# 18650_1S3P_Smart.net
KiCad netlist of a schematic drawn in EAGLE
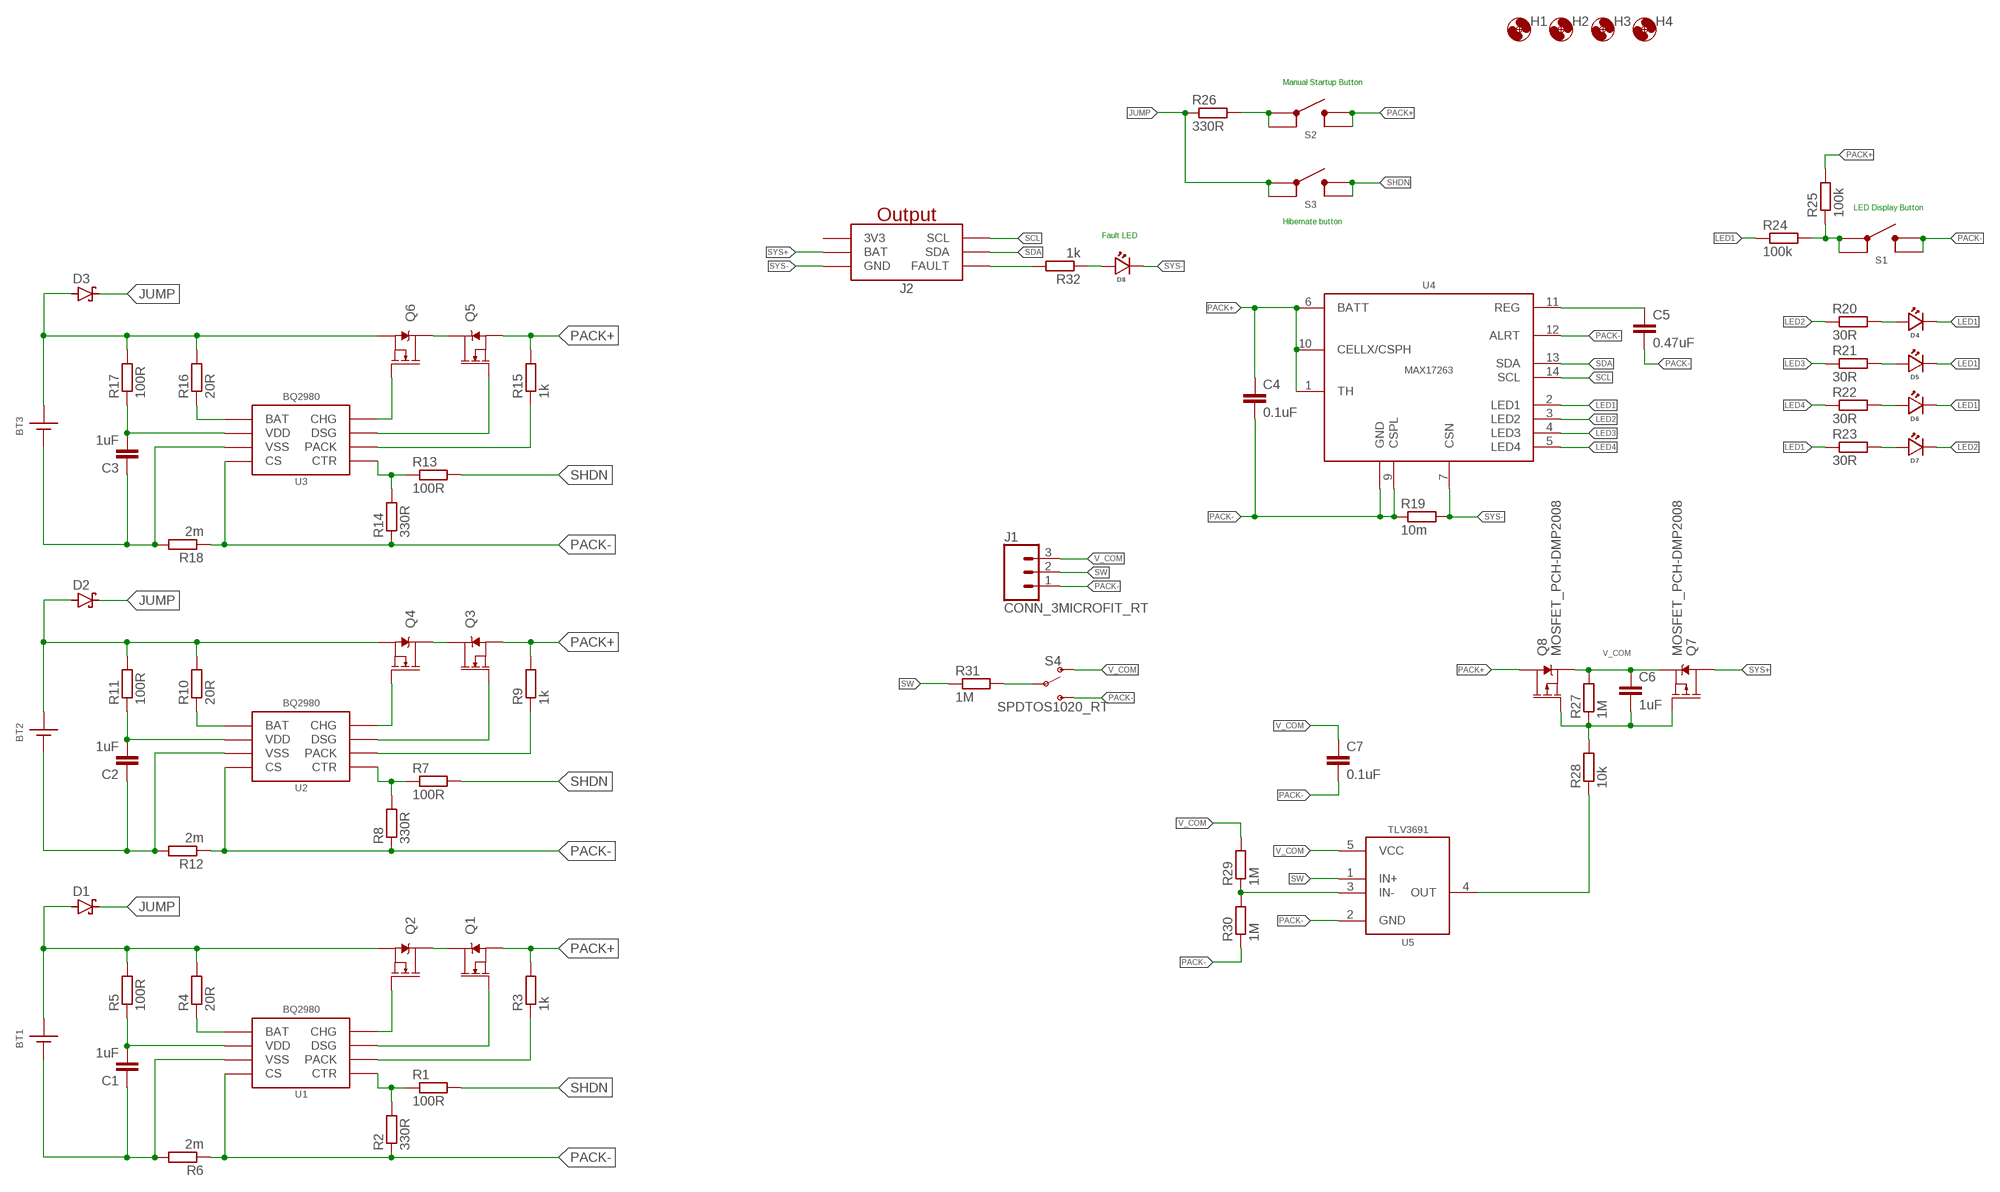
[diagram p0: schematic, sheet 1]

(export (version "E")
  (design (tool "Eeschema 10.0.6"))
  (components
    (comp (ref "BT1")
      (value "186501042P_NOSILK")
      (footprint "eagle-import:BATT_1042P_NOSILK")
      (fields (field (name "MF") "Keystone") (field (name "MPN") "1042P"))
      (libsource (lib "eagle-import") (part "186501042P_NOSILK"))
    )
    (comp (ref "BT2")
      (value "186501042P_NOSILK")
      (footprint "eagle-import:BATT_1042P_NOSILK")
      (fields (field (name "MF") "Keystone") (field (name "MPN") "1042P"))
      (libsource (lib "eagle-import") (part "186501042P_NOSILK"))
    )
    (comp (ref "BT3")
      (value "186501042P_NOSILK")
      (footprint "eagle-import:BATT_1042P_NOSILK")
      (fields (field (name "MF") "Keystone") (field (name "MPN") "1042P"))
      (libsource (lib "eagle-import") (part "186501042P_NOSILK"))
    )
    (comp (ref "C1")
      (value "1uF")
      (footprint "eagle-import:C0603")
      (fields (field (name "MF") "Yaiyo Yuden") (field (name "MPN") "EMK107BJ105KA-T"))
      (libsource (lib "eagle-import") (part "C-EUC06031UF"))
    )
    (comp (ref "C2")
      (value "1uF")
      (footprint "eagle-import:C0603")
      (fields (field (name "MF") "Yaiyo Yuden") (field (name "MPN") "EMK107BJ105KA-T"))
      (libsource (lib "eagle-import") (part "C-EUC06031UF"))
    )
    (comp (ref "C3")
      (value "1uF")
      (footprint "eagle-import:C0603")
      (fields (field (name "MF") "Yaiyo Yuden") (field (name "MPN") "EMK107BJ105KA-T"))
      (libsource (lib "eagle-import") (part "C-EUC06031UF"))
    )
    (comp (ref "C4")
      (value "0.1uF")
      (footprint "eagle-import:C0603")
      (fields (field (name "MF") "Murata") (field (name "MPN") "GCM188R71E104KA57D"))
      (libsource (lib "eagle-import") (part "C-EUC06030.1UF"))
    )
    (comp (ref "C5")
      (value "0.47uF")
      (footprint "eagle-import:C0603")
      (fields (field (name "MF") "Samsung") (field (name "MPN") "CL10B474KA8NNNC"))
      (libsource (lib "eagle-import") (part "C-EUC06030.47UF"))
    )
    (comp (ref "C6")
      (value "1uF")
      (footprint "eagle-import:C0603")
      (fields (field (name "MF") "Yaiyo Yuden") (field (name "MPN") "EMK107BJ105KA-T"))
      (libsource (lib "eagle-import") (part "C-EUC06031UF"))
    )
    (comp (ref "C7")
      (value "0.1uF")
      (footprint "eagle-import:C0603")
      (fields (field (name "MF") "Murata") (field (name "MPN") "GCM188R71E104KA57D"))
      (libsource (lib "eagle-import") (part "C-EUC06030.1UF"))
    )
    (comp (ref "D1")
      (value "DIODE_SCHOTTKYSOD-323")
      (footprint "eagle-import:SOD323-R")
      (fields
        (field (name "DIGIKEY") "BAT54WS-FDICT-ND")
        (field (name "MF") "Diodes Inc")
        (field (name "MPN") "BAT54WS-7-F")
      )
      (libsource (lib "eagle-import") (part "DIODE_SCHOTTKYSOD-323"))
    )
    (comp (ref "D2")
      (value "DIODE_SCHOTTKYSOD-323")
      (footprint "eagle-import:SOD323-R")
      (fields
        (field (name "DIGIKEY") "BAT54WS-FDICT-ND")
        (field (name "MF") "Diodes Inc")
        (field (name "MPN") "BAT54WS-7-F")
      )
      (libsource (lib "eagle-import") (part "DIODE_SCHOTTKYSOD-323"))
    )
    (comp (ref "D3")
      (value "DIODE_SCHOTTKYSOD-323")
      (footprint "eagle-import:SOD323-R")
      (fields
        (field (name "DIGIKEY") "BAT54WS-FDICT-ND")
        (field (name "MF") "Diodes Inc")
        (field (name "MPN") "BAT54WS-7-F")
      )
      (libsource (lib "eagle-import") (part "DIODE_SCHOTTKYSOD-323"))
    )
    (comp (ref "D4")
      (value "LED1206_BOTTOM")
      (footprint "eagle-import:LED_1206_BOTTOM")
      (libsource (lib "eagle-import") (part "LED1206_BOTTOM"))
    )
    (comp (ref "D5")
      (value "LED1206_BOTTOM")
      (footprint "eagle-import:LED_1206_BOTTOM")
      (libsource (lib "eagle-import") (part "LED1206_BOTTOM"))
    )
    (comp (ref "D6")
      (value "LED1206_BOTTOM")
      (footprint "eagle-import:LED_1206_BOTTOM")
      (libsource (lib "eagle-import") (part "LED1206_BOTTOM"))
    )
    (comp (ref "D7")
      (value "LED1206_BOTTOM")
      (footprint "eagle-import:LED_1206_BOTTOM")
      (libsource (lib "eagle-import") (part "LED1206_BOTTOM"))
    )
    (comp (ref "D8")
      (value "LED1206_BOTTOM")
      (footprint "eagle-import:LED_1206_BOTTOM")
      (libsource (lib "eagle-import") (part "LED1206_BOTTOM"))
    )
    (comp (ref "H1")
      (value "MOUNTING_HOLE2_NP")
      (footprint "eagle-import:2_56")
      (fields (field (name "MPN") "DNP"))
      (libsource (lib "eagle-import") (part "MOUNTING_HOLE2_NP"))
    )
    (comp (ref "H2")
      (value "MOUNTING_HOLE2_NP")
      (footprint "eagle-import:2_56")
      (fields (field (name "MPN") "DNP"))
      (libsource (lib "eagle-import") (part "MOUNTING_HOLE2_NP"))
    )
    (comp (ref "H3")
      (value "MOUNTING_HOLE2_NP")
      (footprint "eagle-import:2_56")
      (fields (field (name "MPN") "DNP"))
      (libsource (lib "eagle-import") (part "MOUNTING_HOLE2_NP"))
    )
    (comp (ref "H4")
      (value "MOUNTING_HOLE2_NP")
      (footprint "eagle-import:2_56")
      (fields (field (name "MPN") "DNP"))
      (libsource (lib "eagle-import") (part "MOUNTING_HOLE2_NP"))
    )
    (comp (ref "J1")
      (value "CONN_3MICROFIT_RT")
      (footprint "eagle-import:1X3_MICROFIT_RT")
      (fields (field (name "MF") "Molex") (field (name "MPN") "0436500300"))
      (libsource (lib "eagle-import") (part "CONN_3MICROFIT_RT"))
    )
    (comp (ref "J2")
      (value "GEMS_POWER_PLUGOUTPUT")
      (footprint "eagle-import:2X3_MICROFIT_RT")
      (fields (field (name "DISP") "Output") (field (name "MF") "Molex") (field (name "MPN") "0430450600"))
      (libsource (lib "eagle-import") (part "GEMS_POWER_PLUGOUTPUT"))
    )
    (comp (ref "Q1")
      (value "MOSFET-NCH-AON7522E")
      (footprint "eagle-import:DFN3X3A_8L_EP1_P")
      (fields (field (name "MF") "Alpha & Omega") (field (name "MPN") "AON7522E"))
      (libsource (lib "eagle-import") (part "MOSFET-NCH-AON7522E"))
    )
    (comp (ref "Q2")
      (value "MOSFET-NCH-AON7522E")
      (footprint "eagle-import:DFN3X3A_8L_EP1_P")
      (fields (field (name "MF") "Alpha & Omega") (field (name "MPN") "AON7522E"))
      (libsource (lib "eagle-import") (part "MOSFET-NCH-AON7522E"))
    )
    (comp (ref "Q3")
      (value "MOSFET-NCH-AON7522E")
      (footprint "eagle-import:DFN3X3A_8L_EP1_P")
      (fields (field (name "MF") "Alpha & Omega") (field (name "MPN") "AON7522E"))
      (libsource (lib "eagle-import") (part "MOSFET-NCH-AON7522E"))
    )
    (comp (ref "Q4")
      (value "MOSFET-NCH-AON7522E")
      (footprint "eagle-import:DFN3X3A_8L_EP1_P")
      (fields (field (name "MF") "Alpha & Omega") (field (name "MPN") "AON7522E"))
      (libsource (lib "eagle-import") (part "MOSFET-NCH-AON7522E"))
    )
    (comp (ref "Q5")
      (value "MOSFET-NCH-AON7522E")
      (footprint "eagle-import:DFN3X3A_8L_EP1_P")
      (fields (field (name "MF") "Alpha & Omega") (field (name "MPN") "AON7522E"))
      (libsource (lib "eagle-import") (part "MOSFET-NCH-AON7522E"))
    )
    (comp (ref "Q6")
      (value "MOSFET-NCH-AON7522E")
      (footprint "eagle-import:DFN3X3A_8L_EP1_P")
      (fields (field (name "MF") "Alpha & Omega") (field (name "MPN") "AON7522E"))
      (libsource (lib "eagle-import") (part "MOSFET-NCH-AON7522E"))
    )
    (comp (ref "Q7")
      (value "MOSFET_PCH-DMP2008")
      (footprint "eagle-import:POWERDI3333-8")
      (libsource (lib "eagle-import") (part "MOSFET_PCH-DMP2008"))
    )
    (comp (ref "Q8")
      (value "MOSFET_PCH-DMP2008")
      (footprint "eagle-import:POWERDI3333-8")
      (libsource (lib "eagle-import") (part "MOSFET_PCH-DMP2008"))
    )
    (comp (ref "R1")
      (value "100R")
      (footprint "eagle-import:R0603")
      (fields
        (field (name "MF") "Yageo")
        (field (name "MPN") "RC0603FR-07100RL")
        (field (name "VALUE_PART") "100")
      )
      (libsource (lib "eagle-import") (part "R-EU_R0603100"))
    )
    (comp (ref "R2")
      (value "330R")
      (footprint "eagle-import:R0603")
      (fields
        (field (name "MF") "Yageo")
        (field (name "MPN") "RC0603FR-07330RL")
        (field (name "VALUE_PART") "330")
      )
      (libsource (lib "eagle-import") (part "R-EU_R0603330"))
    )
    (comp (ref "R3")
      (value "1k")
      (footprint "eagle-import:R0603")
      (fields (field (name "MF") "Yageo") (field (name "MPN") "AC0603FR-071KL"))
      (libsource (lib "eagle-import") (part "R-EU_R06031K"))
    )
    (comp (ref "R4")
      (value "20R")
      (footprint "eagle-import:R0603")
      (fields
        (field (name "MF") "Yageo")
        (field (name "MPN") "RC0603FR-0720RL")
        (field (name "VALUE_PART") "20")
      )
      (libsource (lib "eagle-import") (part "R-EU_R060320"))
    )
    (comp (ref "R5")
      (value "100R")
      (footprint "eagle-import:R0603")
      (fields
        (field (name "MF") "Yageo")
        (field (name "MPN") "RC0603FR-07100RL")
        (field (name "VALUE_PART") "100")
      )
      (libsource (lib "eagle-import") (part "R-EU_R0603100"))
    )
    (comp (ref "R6")
      (value "2m")
      (footprint "eagle-import:R0805")
      (fields (field (name "MF") "Rohm") (field (name "MPN") "PMR10EZPFV2L00"))
      (libsource (lib "eagle-import") (part "R-EU_R08050.002"))
    )
    (comp (ref "R7")
      (value "100R")
      (footprint "eagle-import:R0603")
      (fields
        (field (name "MF") "Yageo")
        (field (name "MPN") "RC0603FR-07100RL")
        (field (name "VALUE_PART") "100")
      )
      (libsource (lib "eagle-import") (part "R-EU_R0603100"))
    )
    (comp (ref "R8")
      (value "330R")
      (footprint "eagle-import:R0603")
      (fields
        (field (name "MF") "Yageo")
        (field (name "MPN") "RC0603FR-07330RL")
        (field (name "VALUE_PART") "330")
      )
      (libsource (lib "eagle-import") (part "R-EU_R0603330"))
    )
    (comp (ref "R9")
      (value "1k")
      (footprint "eagle-import:R0603")
      (fields (field (name "MF") "Yageo") (field (name "MPN") "AC0603FR-071KL"))
      (libsource (lib "eagle-import") (part "R-EU_R06031K"))
    )
    (comp (ref "R10")
      (value "20R")
      (footprint "eagle-import:R0603")
      (fields
        (field (name "MF") "Yageo")
        (field (name "MPN") "RC0603FR-0720RL")
        (field (name "VALUE_PART") "20")
      )
      (libsource (lib "eagle-import") (part "R-EU_R060320"))
    )
    (comp (ref "R11")
      (value "100R")
      (footprint "eagle-import:R0603")
      (fields
        (field (name "MF") "Yageo")
        (field (name "MPN") "RC0603FR-07100RL")
        (field (name "VALUE_PART") "100")
      )
      (libsource (lib "eagle-import") (part "R-EU_R0603100"))
    )
    (comp (ref "R12")
      (value "2m")
      (footprint "eagle-import:R0805")
      (fields (field (name "MF") "Rohm") (field (name "MPN") "PMR10EZPFV2L00"))
      (libsource (lib "eagle-import") (part "R-EU_R08050.002"))
    )
    (comp (ref "R13")
      (value "100R")
      (footprint "eagle-import:R0603")
      (fields
        (field (name "MF") "Yageo")
        (field (name "MPN") "RC0603FR-07100RL")
        (field (name "VALUE_PART") "100")
      )
      (libsource (lib "eagle-import") (part "R-EU_R0603100"))
    )
    (comp (ref "R14")
      (value "330R")
      (footprint "eagle-import:R0603")
      (fields
        (field (name "MF") "Yageo")
        (field (name "MPN") "RC0603FR-07330RL")
        (field (name "VALUE_PART") "330")
      )
      (libsource (lib "eagle-import") (part "R-EU_R0603330"))
    )
    (comp (ref "R15")
      (value "1k")
      (footprint "eagle-import:R0603")
      (fields (field (name "MF") "Yageo") (field (name "MPN") "AC0603FR-071KL"))
      (libsource (lib "eagle-import") (part "R-EU_R06031K"))
    )
    (comp (ref "R16")
      (value "20R")
      (footprint "eagle-import:R0603")
      (fields
        (field (name "MF") "Yageo")
        (field (name "MPN") "RC0603FR-0720RL")
        (field (name "VALUE_PART") "20")
      )
      (libsource (lib "eagle-import") (part "R-EU_R060320"))
    )
    (comp (ref "R17")
      (value "100R")
      (footprint "eagle-import:R0603")
      (fields
        (field (name "MF") "Yageo")
        (field (name "MPN") "RC0603FR-07100RL")
        (field (name "VALUE_PART") "100")
      )
      (libsource (lib "eagle-import") (part "R-EU_R0603100"))
    )
    (comp (ref "R18")
      (value "2m")
      (footprint "eagle-import:R0805")
      (fields (field (name "MF") "Rohm") (field (name "MPN") "PMR10EZPFV2L00"))
      (libsource (lib "eagle-import") (part "R-EU_R08050.002"))
    )
    (comp (ref "R19")
      (value "10m")
      (footprint "eagle-import:R0805")
      (fields (field (name "MF") "Bourns") (field (name "MPN") "CRF0805-FZ-R010ELF"))
      (libsource (lib "eagle-import") (part "R-EU_R08050.01"))
    )
    (comp (ref "R20")
      (value "30R")
      (footprint "eagle-import:R0603")
      (fields
        (field (name "MF") "Yageo")
        (field (name "MPN") "RC0603FR-0730RL")
        (field (name "VALUE_PART") "30")
      )
      (libsource (lib "eagle-import") (part "R-EU_R060330"))
    )
    (comp (ref "R21")
      (value "30R")
      (footprint "eagle-import:R0603")
      (fields
        (field (name "MF") "Yageo")
        (field (name "MPN") "RC0603FR-0730RL")
        (field (name "VALUE_PART") "30")
      )
      (libsource (lib "eagle-import") (part "R-EU_R060330"))
    )
    (comp (ref "R22")
      (value "30R")
      (footprint "eagle-import:R0603")
      (fields
        (field (name "MF") "Yageo")
        (field (name "MPN") "RC0603FR-0730RL")
        (field (name "VALUE_PART") "30")
      )
      (libsource (lib "eagle-import") (part "R-EU_R060330"))
    )
    (comp (ref "R23")
      (value "30R")
      (footprint "eagle-import:R0603")
      (fields
        (field (name "MF") "Yageo")
        (field (name "MPN") "RC0603FR-0730RL")
        (field (name "VALUE_PART") "30")
      )
      (libsource (lib "eagle-import") (part "R-EU_R060330"))
    )
    (comp (ref "R24")
      (value "100k")
      (footprint "eagle-import:R0603")
      (fields (field (name "MF") "Yageo") (field (name "MPN") "RC0603FR-07100KL"))
      (libsource (lib "eagle-import") (part "R-EU_R0603100K"))
    )
    (comp (ref "R25")
      (value "100k")
      (footprint "eagle-import:R0603")
      (fields (field (name "MF") "Yageo") (field (name "MPN") "RC0603FR-07100KL"))
      (libsource (lib "eagle-import") (part "R-EU_R0603100K"))
    )
    (comp (ref "R26")
      (value "330R")
      (footprint "eagle-import:R0603")
      (fields
        (field (name "MF") "Yageo")
        (field (name "MPN") "RC0603FR-07330RL")
        (field (name "VALUE_PART") "330")
      )
      (libsource (lib "eagle-import") (part "R-EU_R0603330"))
    )
    (comp (ref "R27")
      (value "1M")
      (footprint "eagle-import:R0603")
      (fields (field (name "MF") "Panasonic") (field (name "MPN") "ERJ-3EKF1004V"))
      (libsource (lib "eagle-import") (part "R-EU_R06031M"))
    )
    (comp (ref "R28")
      (value "10k")
      (footprint "eagle-import:R0603")
      (fields (field (name "MF") "Yageo") (field (name "MPN") "RC0603FR-0710KL"))
      (libsource (lib "eagle-import") (part "R-EU_R060310K"))
    )
    (comp (ref "R29")
      (value "1M")
      (footprint "eagle-import:R0603")
      (fields (field (name "MF") "Panasonic") (field (name "MPN") "ERJ-3EKF1004V"))
      (libsource (lib "eagle-import") (part "R-EU_R06031M"))
    )
    (comp (ref "R30")
      (value "1M")
      (footprint "eagle-import:R0603")
      (fields (field (name "MF") "Panasonic") (field (name "MPN") "ERJ-3EKF1004V"))
      (libsource (lib "eagle-import") (part "R-EU_R06031M"))
    )
    (comp (ref "R31")
      (value "1M")
      (footprint "eagle-import:R0603")
      (fields (field (name "MF") "Panasonic") (field (name "MPN") "ERJ-3EKF1004V"))
      (libsource (lib "eagle-import") (part "R-EU_R06031M"))
    )
    (comp (ref "R32")
      (value "1k")
      (footprint "eagle-import:R0603")
      (fields (field (name "MF") "Yageo") (field (name "MPN") "AC0603FR-071KL"))
      (libsource (lib "eagle-import") (part "R-EU_R06031K"))
    )
    (comp (ref "S1")
      (value "BUTTON6X6_TH")
      (footprint "eagle-import:SWITCH_6MM_TH")
      (fields (field (name "MF") "TE Connectivity") (field (name "MPN") "1825910-6"))
      (libsource (lib "eagle-import") (part "BUTTON6X6_TH"))
    )
    (comp (ref "S2")
      (value "BUTTON6X6_TH")
      (footprint "eagle-import:SWITCH_6MM_TH")
      (fields (field (name "MF") "TE Connectivity") (field (name "MPN") "1825910-6"))
      (libsource (lib "eagle-import") (part "BUTTON6X6_TH"))
    )
    (comp (ref "S3")
      (value "BUTTON6X6_TH")
      (footprint "eagle-import:SWITCH_6MM_TH")
      (fields (field (name "MF") "TE Connectivity") (field (name "MPN") "1825910-6"))
      (libsource (lib "eagle-import") (part "BUTTON6X6_TH"))
    )
    (comp (ref "S4")
      (value "SPDTOS1020_RT")
      (footprint "eagle-import:OS102011MA1QN1")
      (fields (field (name "MF") "C&K") (field (name "MPN") "OS102011MA1QN1"))
      (libsource (lib "eagle-import") (part "SPDTOS1020_RT"))
    )
    (comp (ref "U1")
      (value "BQ2980RUG")
      (footprint "eagle-import:RUG_S-PQFP-N8")
      (fields (field (name "MF") "TI") (field (name "MPN") "BQ298000RUGT"))
      (libsource (lib "eagle-import") (part "BQ2980RUG"))
    )
    (comp (ref "U2")
      (value "BQ2980RUG")
      (footprint "eagle-import:RUG_S-PQFP-N8")
      (fields (field (name "MF") "TI") (field (name "MPN") "BQ298000RUGT"))
      (libsource (lib "eagle-import") (part "BQ2980RUG"))
    )
    (comp (ref "U3")
      (value "BQ2980RUG")
      (footprint "eagle-import:RUG_S-PQFP-N8")
      (fields (field (name "MF") "TI") (field (name "MPN") "BQ298000RUGT"))
      (libsource (lib "eagle-import") (part "BQ2980RUG"))
    )
    (comp (ref "U4")
      (value "MAX17263")
      (footprint "eagle-import:DFN_14_3X3")
      (fields (field (name "MF") "Maxim") (field (name "MPN") "MAX17263LETD+T"))
      (libsource (lib "eagle-import") (part "MAX17263"))
    )
    (comp (ref "U5")
      (value "TLV3691DCK")
      (footprint "eagle-import:DCK_R-PDSO-G5")
      (fields (field (name "MF") "TI") (field (name "MPN") "TLV3691IDCKR"))
      (libsource (lib "eagle-import") (part "TLV3691DCK"))
    )
  )
  (nets
    (net (code "1") (name "/3V3") (class "Default")
      (node (ref "J2") (pin "5") (pinfunction "3V3_5") (pintype "power_in"))
    )
    (net (code "2") (name "JUMP") (class "Default")
      (node (ref "D1") (pin "C") (pinfunction "C_C") (pintype "passive"))
      (node (ref "D2") (pin "C") (pinfunction "C_C") (pintype "passive"))
      (node (ref "D3") (pin "C") (pinfunction "C_C") (pintype "passive"))
      (node (ref "R26") (pin "1") (pinfunction "1_1") (pintype "passive"))
      (node (ref "S3") (pin "1") (pinfunction "1_1") (pintype "bidirectional"))
      (node (ref "S3") (pin "2") (pinfunction "2_2") (pintype "bidirectional"))
    )
    (net (code "3") (name "LED1") (class "Default")
      (node (ref "D4") (pin "CATHODE") (pinfunction "CATHODE_CATHODE") (pintype "power_in"))
      (node (ref "D5") (pin "CATHODE") (pinfunction "CATHODE_CATHODE") (pintype "power_in"))
      (node (ref "D6") (pin "CATHODE") (pinfunction "CATHODE_CATHODE") (pintype "power_in"))
      (node (ref "R23") (pin "1") (pinfunction "1_1") (pintype "passive"))
      (node (ref "R24") (pin "1") (pinfunction "1_1") (pintype "passive"))
      (node (ref "U4") (pin "2") (pinfunction "LED1_2") (pintype "bidirectional"))
    )
    (net (code "4") (name "LED2") (class "Default")
      (node (ref "D7") (pin "CATHODE") (pinfunction "CATHODE_CATHODE") (pintype "power_in"))
      (node (ref "R20") (pin "1") (pinfunction "1_1") (pintype "passive"))
      (node (ref "U4") (pin "3") (pinfunction "LED2_3") (pintype "bidirectional"))
    )
    (net (code "5") (name "LED3") (class "Default")
      (node (ref "R21") (pin "1") (pinfunction "1_1") (pintype "passive"))
      (node (ref "U4") (pin "4") (pinfunction "LED3_4") (pintype "bidirectional"))
    )
    (net (code "6") (name "LED4") (class "Default")
      (node (ref "R22") (pin "1") (pinfunction "1_1") (pintype "passive"))
      (node (ref "U4") (pin "5") (pinfunction "LED4_5") (pintype "bidirectional"))
    )
    (net (code "7") (name "Net-(BT1-+)") (class "Default")
      (node (ref "BT1") (pin "BATT+") (pinfunction "+_BATT+") (pintype "power_in"))
      (node (ref "D1") (pin "A") (pinfunction "A_A") (pintype "passive"))
      (node (ref "Q2") (pin "S@1") (pinfunction "S_S@1") (pintype "bidirectional"))
      (node (ref "Q2") (pin "S@2") (pinfunction "S_S@2") (pintype "bidirectional"))
      (node (ref "Q2") (pin "S@3") (pinfunction "S_S@3") (pintype "bidirectional"))
      (node (ref "R4") (pin "2") (pinfunction "2_2") (pintype "passive"))
      (node (ref "R5") (pin "2") (pinfunction "2_2") (pintype "passive"))
    )
    (net (code "8") (name "Net-(BT1--)") (class "Default")
      (node (ref "BT1") (pin "BATT-") (pinfunction "-_BATT-") (pintype "power_in"))
      (node (ref "C1") (pin "1") (pinfunction "1_1") (pintype "passive"))
      (node (ref "R6") (pin "2") (pinfunction "2_2") (pintype "passive"))
      (node (ref "U1") (pin "3") (pinfunction "VSS_3") (pintype "power_in"))
    )
    (net (code "9") (name "Net-(BT2-+)") (class "Default")
      (node (ref "BT2") (pin "BATT+") (pinfunction "+_BATT+") (pintype "power_in"))
      (node (ref "D2") (pin "A") (pinfunction "A_A") (pintype "passive"))
      (node (ref "Q4") (pin "S@1") (pinfunction "S_S@1") (pintype "bidirectional"))
      (node (ref "Q4") (pin "S@2") (pinfunction "S_S@2") (pintype "bidirectional"))
      (node (ref "Q4") (pin "S@3") (pinfunction "S_S@3") (pintype "bidirectional"))
      (node (ref "R10") (pin "2") (pinfunction "2_2") (pintype "passive"))
      (node (ref "R11") (pin "2") (pinfunction "2_2") (pintype "passive"))
    )
    (net (code "10") (name "Net-(BT2--)") (class "Default")
      (node (ref "BT2") (pin "BATT-") (pinfunction "-_BATT-") (pintype "power_in"))
      (node (ref "C2") (pin "1") (pinfunction "1_1") (pintype "passive"))
      (node (ref "R12") (pin "2") (pinfunction "2_2") (pintype "passive"))
      (node (ref "U2") (pin "3") (pinfunction "VSS_3") (pintype "power_in"))
    )
    (net (code "11") (name "Net-(BT3-+)") (class "Default")
      (node (ref "BT3") (pin "BATT+") (pinfunction "+_BATT+") (pintype "power_in"))
      (node (ref "D3") (pin "A") (pinfunction "A_A") (pintype "passive"))
      (node (ref "Q6") (pin "S@1") (pinfunction "S_S@1") (pintype "bidirectional"))
      (node (ref "Q6") (pin "S@2") (pinfunction "S_S@2") (pintype "bidirectional"))
      (node (ref "Q6") (pin "S@3") (pinfunction "S_S@3") (pintype "bidirectional"))
      (node (ref "R16") (pin "2") (pinfunction "2_2") (pintype "passive"))
      (node (ref "R17") (pin "2") (pinfunction "2_2") (pintype "passive"))
    )
    (net (code "12") (name "Net-(BT3--)") (class "Default")
      (node (ref "BT3") (pin "BATT-") (pinfunction "-_BATT-") (pintype "power_in"))
      (node (ref "C3") (pin "1") (pinfunction "1_1") (pintype "passive"))
      (node (ref "R18") (pin "2") (pinfunction "2_2") (pintype "passive"))
      (node (ref "U3") (pin "3") (pinfunction "VSS_3") (pintype "power_in"))
    )
    (net (code "13") (name "Net-(D4-PadANODE)") (class "Default")
      (node (ref "D4") (pin "ANODE") (pinfunction "ANODE_ANODE") (pintype "power_in"))
      (node (ref "R20") (pin "2") (pinfunction "2_2") (pintype "passive"))
    )
    (net (code "14") (name "Net-(D5-PadANODE)") (class "Default")
      (node (ref "D5") (pin "ANODE") (pinfunction "ANODE_ANODE") (pintype "power_in"))
      (node (ref "R21") (pin "2") (pinfunction "2_2") (pintype "passive"))
    )
    (net (code "15") (name "Net-(D6-PadANODE)") (class "Default")
      (node (ref "D6") (pin "ANODE") (pinfunction "ANODE_ANODE") (pintype "power_in"))
      (node (ref "R22") (pin "2") (pinfunction "2_2") (pintype "passive"))
    )
    (net (code "16") (name "Net-(D7-PadANODE)") (class "Default")
      (node (ref "D7") (pin "ANODE") (pinfunction "ANODE_ANODE") (pintype "power_in"))
      (node (ref "R23") (pin "2") (pinfunction "2_2") (pintype "passive"))
    )
    (net (code "17") (name "Net-(D8-PadANODE)") (class "Default")
      (node (ref "D8") (pin "ANODE") (pinfunction "ANODE_ANODE") (pintype "power_in"))
      (node (ref "R32") (pin "1") (pinfunction "1_1") (pintype "passive"))
    )
    (net (code "18") (name "Net-(J2-FAULT)") (class "Default")
      (node (ref "J2") (pin "1") (pinfunction "FAULT_1") (pintype "bidirectional"))
      (node (ref "R32") (pin "2") (pinfunction "2_2") (pintype "passive"))
    )
    (net (code "19") (name "Net-(Q1-PadD)") (class "Default")
      (node (ref "Q1") (pin "D") (pinfunction "D_D") (pintype "bidirectional"))
      (node (ref "Q2") (pin "D") (pinfunction "D_D") (pintype "bidirectional"))
    )
    (net (code "20") (name "Net-(Q3-PadD)") (class "Default")
      (node (ref "Q3") (pin "D") (pinfunction "D_D") (pintype "bidirectional"))
      (node (ref "Q4") (pin "D") (pinfunction "D_D") (pintype "bidirectional"))
    )
    (net (code "21") (name "Net-(Q5-PadD)") (class "Default")
      (node (ref "Q5") (pin "D") (pinfunction "D_D") (pintype "bidirectional"))
      (node (ref "Q6") (pin "D") (pinfunction "D_D") (pintype "bidirectional"))
    )
    (net (code "22") (name "Net-(Q7-G)") (class "Default")
      (node (ref "C6") (pin "2") (pinfunction "2_2") (pintype "passive"))
      (node (ref "Q7") (pin "4") (pinfunction "G_4") (pintype "bidirectional"))
      (node (ref "Q8") (pin "4") (pinfunction "G_4") (pintype "bidirectional"))
      (node (ref "R27") (pin "1") (pinfunction "1_1") (pintype "passive"))
      (node (ref "R28") (pin "2") (pinfunction "2_2") (pintype "passive"))
    )
    (net (code "23") (name "Net-(R24-Pad2)") (class "Default")
      (node (ref "R24") (pin "2") (pinfunction "2_2") (pintype "passive"))
      (node (ref "R25") (pin "1") (pinfunction "1_1") (pintype "passive"))
      (node (ref "S1") (pin "1") (pinfunction "1_1") (pintype "bidirectional"))
      (node (ref "S1") (pin "2") (pinfunction "2_2") (pintype "bidirectional"))
    )
    (net (code "24") (name "Net-(R26-Pad2)") (class "Default")
      (node (ref "R26") (pin "2") (pinfunction "2_2") (pintype "passive"))
      (node (ref "S2") (pin "1") (pinfunction "1_1") (pintype "bidirectional"))
      (node (ref "S2") (pin "2") (pinfunction "2_2") (pintype "bidirectional"))
    )
    (net (code "25") (name "Net-(S4-P)") (class "Default")
      (node (ref "R31") (pin "2") (pinfunction "2_2") (pintype "passive"))
      (node (ref "S4") (pin "2") (pinfunction "P_2") (pintype "passive"))
    )
    (net (code "26") (name "Net-(U1-BAT)") (class "Default")
      (node (ref "R4") (pin "1") (pinfunction "1_1") (pintype "passive"))
      (node (ref "U1") (pin "1") (pinfunction "BAT_1") (pintype "power_in"))
    )
    (net (code "27") (name "Net-(U1-CHG)") (class "Default")
      (node (ref "Q2") (pin "G") (pinfunction "G_G") (pintype "bidirectional"))
      (node (ref "U1") (pin "8") (pinfunction "CHG_8") (pintype "output"))
    )
    (net (code "28") (name "Net-(U1-CTR)") (class "Default")
      (node (ref "R1") (pin "1") (pinfunction "1_1") (pintype "passive"))
      (node (ref "R2") (pin "2") (pinfunction "2_2") (pintype "passive"))
      (node (ref "U1") (pin "5") (pinfunction "CTR_5") (pintype "input"))
    )
    (net (code "29") (name "Net-(U1-DSG)") (class "Default")
      (node (ref "Q1") (pin "G") (pinfunction "G_G") (pintype "bidirectional"))
      (node (ref "U1") (pin "7") (pinfunction "DSG_7") (pintype "output"))
    )
    (net (code "30") (name "Net-(U1-PACK)") (class "Default")
      (node (ref "R3") (pin "1") (pinfunction "1_1") (pintype "passive"))
      (node (ref "U1") (pin "6") (pinfunction "PACK_6") (pintype "input"))
    )
    (net (code "31") (name "Net-(U1-VDD)") (class "Default")
      (node (ref "C1") (pin "2") (pinfunction "2_2") (pintype "passive"))
      (node (ref "R5") (pin "1") (pinfunction "1_1") (pintype "passive"))
      (node (ref "U1") (pin "2") (pinfunction "VDD_2") (pintype "power_in"))
    )
    (net (code "32") (name "Net-(U2-BAT)") (class "Default")
      (node (ref "R10") (pin "1") (pinfunction "1_1") (pintype "passive"))
      (node (ref "U2") (pin "1") (pinfunction "BAT_1") (pintype "power_in"))
    )
    (net (code "33") (name "Net-(U2-CHG)") (class "Default")
      (node (ref "Q4") (pin "G") (pinfunction "G_G") (pintype "bidirectional"))
      (node (ref "U2") (pin "8") (pinfunction "CHG_8") (pintype "output"))
    )
    (net (code "34") (name "Net-(U2-CTR)") (class "Default")
      (node (ref "R7") (pin "1") (pinfunction "1_1") (pintype "passive"))
      (node (ref "R8") (pin "2") (pinfunction "2_2") (pintype "passive"))
      (node (ref "U2") (pin "5") (pinfunction "CTR_5") (pintype "input"))
    )
    (net (code "35") (name "Net-(U2-DSG)") (class "Default")
      (node (ref "Q3") (pin "G") (pinfunction "G_G") (pintype "bidirectional"))
      (node (ref "U2") (pin "7") (pinfunction "DSG_7") (pintype "output"))
    )
    (net (code "36") (name "Net-(U2-PACK)") (class "Default")
      (node (ref "R9") (pin "1") (pinfunction "1_1") (pintype "passive"))
      (node (ref "U2") (pin "6") (pinfunction "PACK_6") (pintype "input"))
    )
    (net (code "37") (name "Net-(U2-VDD)") (class "Default")
      (node (ref "C2") (pin "2") (pinfunction "2_2") (pintype "passive"))
      (node (ref "R11") (pin "1") (pinfunction "1_1") (pintype "passive"))
      (node (ref "U2") (pin "2") (pinfunction "VDD_2") (pintype "power_in"))
    )
    (net (code "38") (name "Net-(U3-BAT)") (class "Default")
      (node (ref "R16") (pin "1") (pinfunction "1_1") (pintype "passive"))
      (node (ref "U3") (pin "1") (pinfunction "BAT_1") (pintype "power_in"))
    )
    (net (code "39") (name "Net-(U3-CHG)") (class "Default")
      (node (ref "Q6") (pin "G") (pinfunction "G_G") (pintype "bidirectional"))
      (node (ref "U3") (pin "8") (pinfunction "CHG_8") (pintype "output"))
    )
    (net (code "40") (name "Net-(U3-CTR)") (class "Default")
      (node (ref "R13") (pin "1") (pinfunction "1_1") (pintype "passive"))
      (node (ref "R14") (pin "2") (pinfunction "2_2") (pintype "passive"))
      (node (ref "U3") (pin "5") (pinfunction "CTR_5") (pintype "input"))
    )
    (net (code "41") (name "Net-(U3-DSG)") (class "Default")
      (node (ref "Q5") (pin "G") (pinfunction "G_G") (pintype "bidirectional"))
      (node (ref "U3") (pin "7") (pinfunction "DSG_7") (pintype "output"))
    )
    (net (code "42") (name "Net-(U3-PACK)") (class "Default")
      (node (ref "R15") (pin "1") (pinfunction "1_1") (pintype "passive"))
      (node (ref "U3") (pin "6") (pinfunction "PACK_6") (pintype "input"))
    )
    (net (code "43") (name "Net-(U3-VDD)") (class "Default")
      (node (ref "C3") (pin "2") (pinfunction "2_2") (pintype "passive"))
      (node (ref "R17") (pin "1") (pinfunction "1_1") (pintype "passive"))
      (node (ref "U3") (pin "2") (pinfunction "VDD_2") (pintype "power_in"))
    )
    (net (code "44") (name "Net-(U4-REG)") (class "Default")
      (node (ref "C5") (pin "1") (pinfunction "1_1") (pintype "passive"))
      (node (ref "U4") (pin "11") (pinfunction "REG_11") (pintype "power_in"))
    )
    (net (code "45") (name "Net-(U5-IN-)") (class "Default")
      (node (ref "R29") (pin "1") (pinfunction "1_1") (pintype "passive"))
      (node (ref "R30") (pin "2") (pinfunction "2_2") (pintype "passive"))
      (node (ref "U5") (pin "3") (pinfunction "IN-_3") (pintype "input"))
    )
    (net (code "46") (name "Net-(U5-OUT)") (class "Default")
      (node (ref "R28") (pin "1") (pinfunction "1_1") (pintype "passive"))
      (node (ref "U5") (pin "4") (pinfunction "OUT_4") (pintype "output"))
    )
    (net (code "47") (name "PACK+") (class "Default")
      (node (ref "C4") (pin "1") (pinfunction "1_1") (pintype "passive"))
      (node (ref "Q1") (pin "S@1") (pinfunction "S_S@1") (pintype "bidirectional"))
      (node (ref "Q1") (pin "S@2") (pinfunction "S_S@2") (pintype "bidirectional"))
      (node (ref "Q1") (pin "S@3") (pinfunction "S_S@3") (pintype "bidirectional"))
      (node (ref "Q3") (pin "S@1") (pinfunction "S_S@1") (pintype "bidirectional"))
      (node (ref "Q3") (pin "S@2") (pinfunction "S_S@2") (pintype "bidirectional"))
      (node (ref "Q3") (pin "S@3") (pinfunction "S_S@3") (pintype "bidirectional"))
      (node (ref "Q5") (pin "S@1") (pinfunction "S_S@1") (pintype "bidirectional"))
      (node (ref "Q5") (pin "S@2") (pinfunction "S_S@2") (pintype "bidirectional"))
      (node (ref "Q5") (pin "S@3") (pinfunction "S_S@3") (pintype "bidirectional"))
      (node (ref "Q8") (pin "EP@1") (pinfunction "D_EP@1") (pintype "bidirectional"))
      (node (ref "Q8") (pin "EP@2") (pinfunction "D_EP@2") (pintype "bidirectional"))
      (node (ref "Q8") (pin "EP@3") (pinfunction "D_EP@3") (pintype "bidirectional"))
      (node (ref "Q8") (pin "EP@4") (pinfunction "D_EP@4") (pintype "bidirectional"))
      (node (ref "Q8") (pin "EP@5") (pinfunction "D_EP@5") (pintype "bidirectional"))
      (node (ref "R15") (pin "2") (pinfunction "2_2") (pintype "passive"))
      (node (ref "R25") (pin "2") (pinfunction "2_2") (pintype "passive"))
      (node (ref "R3") (pin "2") (pinfunction "2_2") (pintype "passive"))
      (node (ref "R9") (pin "2") (pinfunction "2_2") (pintype "passive"))
      (node (ref "S2") (pin "3") (pinfunction "3_3") (pintype "bidirectional"))
      (node (ref "S2") (pin "4") (pinfunction "4_4") (pintype "bidirectional"))
      (node (ref "U4") (pin "1") (pinfunction "TH_1") (pintype "input"))
      (node (ref "U4") (pin "10") (pinfunction "CELLX/CSPH_10") (pintype "input"))
      (node (ref "U4") (pin "6") (pinfunction "BATT_6") (pintype "power_in"))
    )
    (net (code "48") (name "PACK-") (class "Default")
      (node (ref "C4") (pin "2") (pinfunction "2_2") (pintype "passive"))
      (node (ref "C5") (pin "2") (pinfunction "2_2") (pintype "passive"))
      (node (ref "C7") (pin "2") (pinfunction "2_2") (pintype "passive"))
      (node (ref "J1") (pin "1") (pinfunction "1_1") (pintype "passive"))
      (node (ref "R12") (pin "1") (pinfunction "1_1") (pintype "passive"))
      (node (ref "R14") (pin "1") (pinfunction "1_1") (pintype "passive"))
      (node (ref "R18") (pin "1") (pinfunction "1_1") (pintype "passive"))
      (node (ref "R19") (pin "1") (pinfunction "1_1") (pintype "passive"))
      (node (ref "R2") (pin "1") (pinfunction "1_1") (pintype "passive"))
      (node (ref "R30") (pin "1") (pinfunction "1_1") (pintype "passive"))
      (node (ref "R6") (pin "1") (pinfunction "1_1") (pintype "passive"))
      (node (ref "R8") (pin "1") (pinfunction "1_1") (pintype "passive"))
      (node (ref "S1") (pin "3") (pinfunction "3_3") (pintype "bidirectional"))
      (node (ref "S1") (pin "4") (pinfunction "4_4") (pintype "bidirectional"))
      (node (ref "S4") (pin "3") (pinfunction "S_3") (pintype "passive"))
      (node (ref "U1") (pin "4") (pinfunction "CS_4") (pintype "input"))
      (node (ref "U2") (pin "4") (pinfunction "CS_4") (pintype "input"))
      (node (ref "U3") (pin "4") (pinfunction "CS_4") (pintype "input"))
      (node (ref "U4") (pin "12") (pinfunction "ALRT_12") (pintype "open_collector"))
      (node (ref "U4") (pin "8") (pinfunction "GND_8") (pintype "power_in"))
      (node (ref "U4") (pin "9") (pinfunction "CSPL_9") (pintype "input"))
      (node (ref "U4") (pin "EP") (pinfunction "GND_EP") (pintype "power_in"))
      (node (ref "U5") (pin "2") (pinfunction "GND_2") (pintype "power_in"))
    )
    (net (code "49") (name "SCL") (class "Default")
      (node (ref "J2") (pin "4") (pinfunction "SCL_4") (pintype "bidirectional"))
      (node (ref "U4") (pin "14") (pinfunction "SCL_14") (pintype "input"))
    )
    (net (code "50") (name "SDA") (class "Default")
      (node (ref "J2") (pin "6") (pinfunction "SDA_6") (pintype "bidirectional"))
      (node (ref "U4") (pin "13") (pinfunction "SDA_13") (pintype "bidirectional"))
    )
    (net (code "51") (name "SHDN") (class "Default")
      (node (ref "R1") (pin "2") (pinfunction "2_2") (pintype "passive"))
      (node (ref "R13") (pin "2") (pinfunction "2_2") (pintype "passive"))
      (node (ref "R7") (pin "2") (pinfunction "2_2") (pintype "passive"))
      (node (ref "S3") (pin "3") (pinfunction "3_3") (pintype "bidirectional"))
      (node (ref "S3") (pin "4") (pinfunction "4_4") (pintype "bidirectional"))
    )
    (net (code "52") (name "SW") (class "Default")
      (node (ref "J1") (pin "2") (pinfunction "2_2") (pintype "passive"))
      (node (ref "R31") (pin "1") (pinfunction "1_1") (pintype "passive"))
      (node (ref "U5") (pin "1") (pinfunction "IN+_1") (pintype "input"))
    )
    (net (code "53") (name "SYS+") (class "Default")
      (node (ref "J2") (pin "3") (pinfunction "BAT_3") (pintype "power_in"))
      (node (ref "Q7") (pin "EP@1") (pinfunction "D_EP@1") (pintype "bidirectional"))
      (node (ref "Q7") (pin "EP@2") (pinfunction "D_EP@2") (pintype "bidirectional"))
      (node (ref "Q7") (pin "EP@3") (pinfunction "D_EP@3") (pintype "bidirectional"))
      (node (ref "Q7") (pin "EP@4") (pinfunction "D_EP@4") (pintype "bidirectional"))
      (node (ref "Q7") (pin "EP@5") (pinfunction "D_EP@5") (pintype "bidirectional"))
    )
    (net (code "54") (name "SYS-") (class "Default")
      (node (ref "D8") (pin "CATHODE") (pinfunction "CATHODE_CATHODE") (pintype "power_in"))
      (node (ref "J2") (pin "2") (pinfunction "GND_2") (pintype "power_in"))
      (node (ref "R19") (pin "2") (pinfunction "2_2") (pintype "passive"))
      (node (ref "U4") (pin "7") (pinfunction "CSN_7") (pintype "input"))
    )
    (net (code "55") (name "V_COM") (class "Default")
      (node (ref "C6") (pin "1") (pinfunction "1_1") (pintype "passive"))
      (node (ref "C7") (pin "1") (pinfunction "1_1") (pintype "passive"))
      (node (ref "J1") (pin "3") (pinfunction "3_3") (pintype "passive"))
      (node (ref "Q7") (pin "1") (pinfunction "S_1") (pintype "bidirectional"))
      (node (ref "Q7") (pin "2") (pinfunction "S_2") (pintype "bidirectional"))
      (node (ref "Q7") (pin "3") (pinfunction "S_3") (pintype "bidirectional"))
      (node (ref "Q8") (pin "1") (pinfunction "S_1") (pintype "bidirectional"))
      (node (ref "Q8") (pin "2") (pinfunction "S_2") (pintype "bidirectional"))
      (node (ref "Q8") (pin "3") (pinfunction "S_3") (pintype "bidirectional"))
      (node (ref "R27") (pin "2") (pinfunction "2_2") (pintype "passive"))
      (node (ref "R29") (pin "2") (pinfunction "2_2") (pintype "passive"))
      (node (ref "S4") (pin "1") (pinfunction "O_1") (pintype "passive"))
      (node (ref "U5") (pin "5") (pinfunction "VCC_5") (pintype "power_in"))
    )
  )
)
